# CAN_Transceiver.net
KiCad netlist of a schematic drawn in Altium Designer
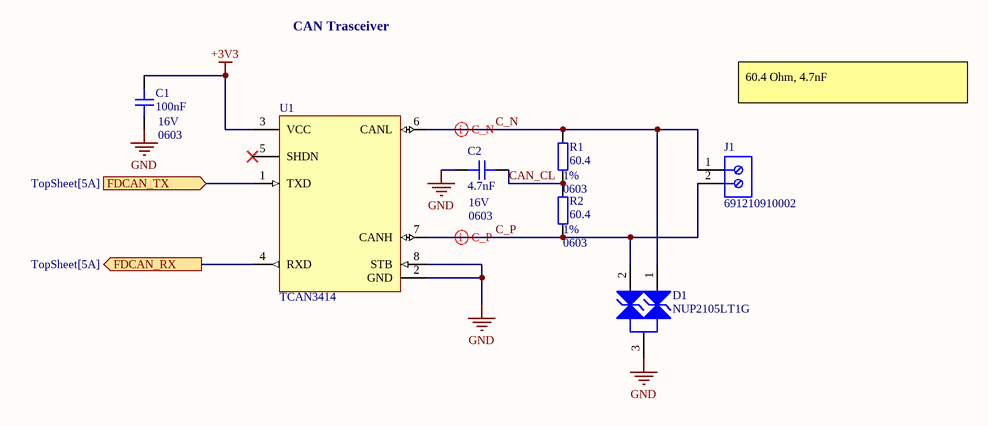
[diagram p0: CAN_Transceiver.SchDoc]

(export (version "E")
  (design (tool "Eeschema 10.0.6"))
  (components
    (comp (ref "C1")
      (value "100nF")
      (footprint "0603_C")
      (description "CAP CER 0.1UF 16V X7R 0603")
      (fields
        (field (name "VOLTAGE - RATED") "16V")
        (field (name "TOLERANCE") "10%")
        (field (name "PACKAGE / CASE") "0603")
        (field (name "MANUFACTURE PART NUMBER") "KGM15AR71C104KM")
      )
      (libsource (lib "Aleksandra Popova") (part "Capacitor - Non Polarized"))
    )
    (comp (ref "C2")
      (value "4.7nF")
      (footprint "0603_C")
      (description "CAP CER 4700PF 16V X7R 0603")
      (fields
        (field (name "MANUFACTURE PART NUMBER") "KGM15AR71C472KT")
        (field (name "VOLTAGE - RATED") "16V")
        (field (name "PACKAGE / CASE") "0603")
        (field (name "TOLERANCE") "10%")
      )
      (libsource (lib "Aleksandra Popova") (part "Capacitor - Non Polarized"))
    )
    (comp (ref "D1")
      (value "NUP2105LT1G")
      (footprint "ONSC-SOT-23-3-318-08_V")
      (description "Dual Line CAN Bus Protector, 3-Pin SOT-23, Pb-Free, Tape and Reel")
      (fields (field (name "MANUFACTURER") "On Semiconductor"))
      (libsource (lib "Altium Content Vault") (part "ONSC-NUP21X5X-SOT-23-3-318-08"))
    )
    (comp (ref "J1")
      (value "691210910002")
      (footprint "691210910002")
      (libsource (lib "Altium Content Vault") (part "TBL - 1R - 02P - Screw"))
    )
    (comp (ref "R1")
      (value "60.4")
      (footprint "0603_R")
      (description "RES 60.4 OHM 1% 1/10W 0603")
      (fields
        (field (name "MANUFACTURE PART NUMBER") "RC0603FR-0760R4L")
        (field (name "TOLERANCE") "1%")
        (field (name "PACKAGE / CASE") "0603")
      )
      (libsource (lib "Aleksandra Popova") (part "Resistor - Standard"))
    )
    (comp (ref "R2")
      (value "60.4")
      (footprint "0603_R")
      (description "RES 60.4 OHM 1% 1/10W 0603")
      (fields
        (field (name "MANUFACTURE PART NUMBER") "RC0603FR-0760R4L")
        (field (name "TOLERANCE") "1%")
        (field (name "PACKAGE / CASE") "0603")
      )
      (libsource (lib "Aleksandra Popova") (part "Resistor - Standard"))
    )
    (comp (ref "U1") (value "TCAN3414") (footprint "SOIC-8NB") (libsource (lib "Schlib2") (part "TCAN3414")))
  )
  (nets
    (net (code "1") (name "+3V3") (class "Default")
      (node (ref "C1") (pin "2") (pinfunction "2_2") (pintype "passive"))
      (node (ref "U1") (pin "3") (pinfunction "VCC_3") (pintype "passive"))
    )
    (net (code "2") (name "/CAN_CL") (class "Default")
      (node (ref "C2") (pin "2") (pinfunction "2_2") (pintype "passive"))
      (node (ref "R1") (pin "1") (pinfunction "1_1") (pintype "passive"))
      (node (ref "R2") (pin "2") (pinfunction "2_2") (pintype "passive"))
    )
    (net (code "3") (name "/C_N") (class "Default")
      (node (ref "D1") (pin "1") (pinfunction "K_1") (pintype "passive"))
      (node (ref "J1") (pin "1") (pinfunction "1_1") (pintype "passive"))
      (node (ref "R1") (pin "2") (pinfunction "2_2") (pintype "passive"))
      (node (ref "U1") (pin "6") (pinfunction "CANL_6") (pintype "bidirectional"))
    )
    (net (code "4") (name "/C_P") (class "Default")
      (node (ref "D1") (pin "2") (pinfunction "K_2") (pintype "passive"))
      (node (ref "J1") (pin "2") (pinfunction "2_2") (pintype "passive"))
      (node (ref "R2") (pin "1") (pinfunction "1_1") (pintype "passive"))
      (node (ref "U1") (pin "7") (pinfunction "CANH_7") (pintype "bidirectional"))
    )
    (net (code "5") (name "/FDCAN_RX") (class "Default")
      (node (ref "U1") (pin "4") (pinfunction "RXD_4") (pintype "output"))
    )
    (net (code "6") (name "/FDCAN_TX") (class "Default")
      (node (ref "U1") (pin "1") (pinfunction "TXD_1") (pintype "input"))
    )
    (net (code "7") (name "GND") (class "Default")
      (node (ref "C1") (pin "1") (pinfunction "1_1") (pintype "passive"))
      (node (ref "C2") (pin "1") (pinfunction "1_1") (pintype "passive"))
      (node (ref "D1") (pin "3") (pinfunction "K_3") (pintype "passive"))
      (node (ref "U1") (pin "2") (pinfunction "GND_2") (pintype "passive"))
      (node (ref "U1") (pin "8") (pinfunction "STB_8") (pintype "input"))
    )
    (net (code "8") (name "unconnected-(U1-SHDN-Pad5)") (class "Default")
      (node (ref "U1") (pin "5") (pinfunction "SHDN_5") (pintype "passive+no_connect"))
    )
  )
)
